# STM32F103.net
KiCad netlist of a schematic drawn in Altium Designer
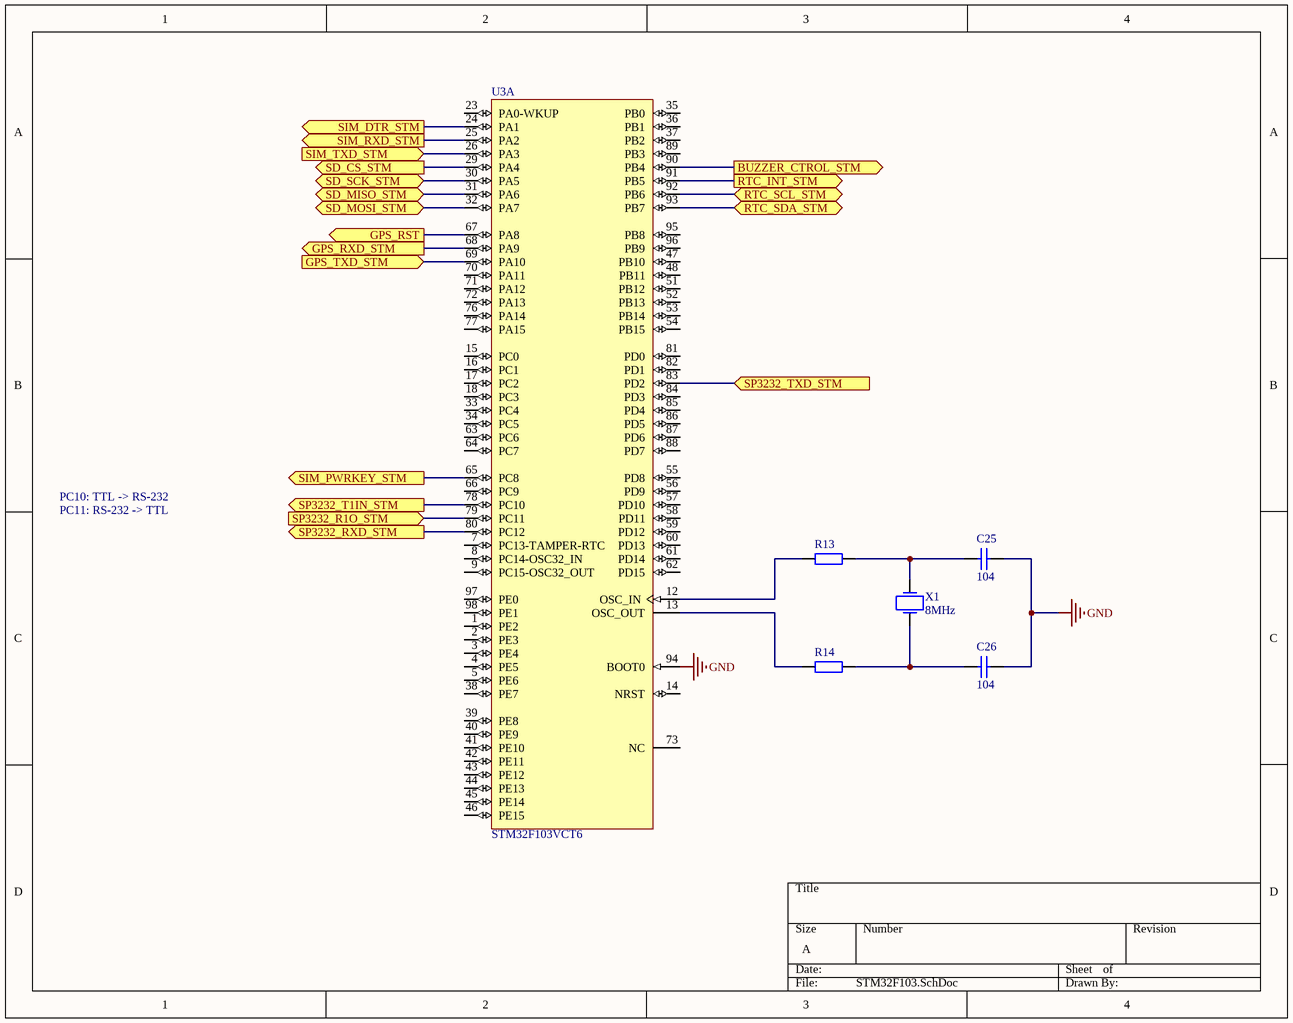
[diagram p0: STM32F103.SchDoc]

(export (version "E")
  (design (tool "Eeschema 10.0.6"))
  (components
    (comp (ref "C25")
      (value "104")
      (footprint "0805")
      (description "Capacitor (Semiconductor SIM Model)")
      (fields (field (name "PUBLISHER") "Altium Limited"))
      (libsource (lib "Devzone_SCHLib") (part "Cap 104_SMD"))
    )
    (comp (ref "C26")
      (value "104")
      (footprint "0805")
      (description "Capacitor (Semiconductor SIM Model)")
      (fields (field (name "PUBLISHER") "Altium Limited"))
      (libsource (lib "Devzone_SCHLib") (part "Cap 104_SMD"))
    )
    (comp (ref "R13")
      (value "~")
      (footprint "RES-1/4W")
      (description "Resistor R1/4W")
      (libsource (lib "KhanhBK_Library_4") (part "R"))
    )
    (comp (ref "R14")
      (value "~")
      (footprint "RES-1/4W")
      (description "Resistor R1/4W")
      (libsource (lib "KhanhBK_Library_4") (part "R"))
    )
    (comp (ref "U3")
      (value "STM32F103VCT6")
      (footprint "STM-LQFP100_M")
      (libsource (lib "KhanhBK_Library_4") (part "STM32F103VCT6"))
    )
    (comp (ref "X1")
      (value "8MHz")
      (footprint "XTAL_THG_HC49/US")
      (description "CRYSTAL 8.0000MHZ 12PF T/H")
      (fields
        (field (name "MANUFACTURER") "TXC CORPORATION")
        (field (name "MANUFACTURER PART NUMBER") "9B-8.000MAAE-B")
      )
      (libsource (lib "KhanhBK_SCH_Lib_6") (part "XTAL_9B-8.000MAAE-B"))
    )
  )
  (nets
    (net (code "1") (name "/BUZZER_CTROL_STM") (class "Default")
      (node (ref "U3") (pin "90") (pinfunction "PB4_90") (pintype "bidirectional"))
    )
    (net (code "2") (name "/GPS_RST") (class "Default")
      (node (ref "U3") (pin "67") (pinfunction "PA8_67") (pintype "bidirectional"))
    )
    (net (code "3") (name "/GPS_RXD_STM") (class "Default")
      (node (ref "U3") (pin "68") (pinfunction "PA9_68") (pintype "bidirectional"))
    )
    (net (code "4") (name "/GPS_TXD_STM") (class "Default")
      (node (ref "U3") (pin "69") (pinfunction "PA10_69") (pintype "bidirectional"))
    )
    (net (code "5") (name "/RTC_INT_STM") (class "Default")
      (node (ref "U3") (pin "91") (pinfunction "PB5_91") (pintype "bidirectional"))
    )
    (net (code "6") (name "/RTC_SCL_STM") (class "Default")
      (node (ref "U3") (pin "92") (pinfunction "PB6_92") (pintype "bidirectional"))
    )
    (net (code "7") (name "/RTC_SDA_STM") (class "Default")
      (node (ref "U3") (pin "93") (pinfunction "PB7_93") (pintype "bidirectional"))
    )
    (net (code "8") (name "/SD_CS_STM") (class "Default")
      (node (ref "U3") (pin "29") (pinfunction "PA4_29") (pintype "bidirectional"))
    )
    (net (code "9") (name "/SD_MISO_STM") (class "Default")
      (node (ref "U3") (pin "31") (pinfunction "PA6_31") (pintype "bidirectional"))
    )
    (net (code "10") (name "/SD_MOSI_STM") (class "Default")
      (node (ref "U3") (pin "32") (pinfunction "PA7_32") (pintype "bidirectional"))
    )
    (net (code "11") (name "/SD_SCK_STM") (class "Default")
      (node (ref "U3") (pin "30") (pinfunction "PA5_30") (pintype "bidirectional"))
    )
    (net (code "12") (name "/SIM_DTR_STM") (class "Default")
      (node (ref "U3") (pin "24") (pinfunction "PA1_24") (pintype "bidirectional"))
    )
    (net (code "13") (name "/SIM_PWRKEY_STM") (class "Default")
      (node (ref "U3") (pin "65") (pinfunction "PC8_65") (pintype "bidirectional"))
    )
    (net (code "14") (name "/SIM_RXD_STM") (class "Default")
      (node (ref "U3") (pin "25") (pinfunction "PA2_25") (pintype "bidirectional"))
    )
    (net (code "15") (name "/SIM_TXD_STM") (class "Default")
      (node (ref "U3") (pin "26") (pinfunction "PA3_26") (pintype "bidirectional"))
    )
    (net (code "16") (name "/SP3232_R1O_STM") (class "Default")
      (node (ref "U3") (pin "79") (pinfunction "PC11_79") (pintype "bidirectional"))
    )
    (net (code "17") (name "/SP3232_RXD_STM") (class "Default")
      (node (ref "U3") (pin "80") (pinfunction "PC12_80") (pintype "bidirectional"))
    )
    (net (code "18") (name "/SP3232_T1IN_STM") (class "Default")
      (node (ref "U3") (pin "78") (pinfunction "PC10_78") (pintype "bidirectional"))
    )
    (net (code "19") (name "/SP3232_TXD_STM") (class "Default")
      (node (ref "U3") (pin "83") (pinfunction "PD2_83") (pintype "bidirectional"))
    )
    (net (code "20") (name "GND") (class "Default")
      (node (ref "C25") (pin "2") (pintype "passive"))
      (node (ref "C26") (pin "2") (pintype "passive"))
      (node (ref "U3") (pin "94") (pinfunction "BOOT0_94") (pintype "input"))
    )
    (net (code "21") (name "Net-(U3A-OSC_IN)") (class "Default")
      (node (ref "R13") (pin "2") (pinfunction "2_2") (pintype "passive"))
      (node (ref "U3") (pin "12") (pinfunction "OSC_IN_12") (pintype "input"))
    )
    (net (code "22") (name "Net-(U3A-OSC_OUT)") (class "Default")
      (node (ref "R14") (pin "2") (pinfunction "2_2") (pintype "passive"))
      (node (ref "U3") (pin "13") (pinfunction "OSC_OUT_13") (pintype "passive"))
    )
    (net (code "23") (name "Net-(X1-OSC1)") (class "Default")
      (node (ref "C26") (pin "1") (pintype "passive"))
      (node (ref "R14") (pin "1") (pinfunction "1_1") (pintype "passive"))
      (node (ref "X1") (pin "1") (pinfunction "OSC1_1") (pintype "passive"))
    )
    (net (code "24") (name "Net-(X1-OSC2)") (class "Default")
      (node (ref "C25") (pin "1") (pintype "passive"))
      (node (ref "R13") (pin "1") (pinfunction "1_1") (pintype "passive"))
      (node (ref "X1") (pin "2") (pinfunction "OSC2_2") (pintype "passive"))
    )
    (net (code "25") (name "unconnected-(U3A-NC-Pad73)") (class "Default")
      (node (ref "U3") (pin "73") (pinfunction "NC_73") (pintype "passive"))
    )
    (net (code "26") (name "unconnected-(U3A-NRST-Pad14)") (class "Default")
      (node (ref "U3") (pin "14") (pinfunction "NRST_14") (pintype "bidirectional"))
    )
    (net (code "27") (name "unconnected-(U3A-PA0-WKUP-Pad23)") (class "Default")
      (node (ref "U3") (pin "23") (pinfunction "PA0-WKUP_23") (pintype "bidirectional"))
    )
    (net (code "28") (name "unconnected-(U3A-PA11-Pad70)") (class "Default")
      (node (ref "U3") (pin "70") (pinfunction "PA11_70") (pintype "bidirectional"))
    )
    (net (code "29") (name "unconnected-(U3A-PA12-Pad71)") (class "Default")
      (node (ref "U3") (pin "71") (pinfunction "PA12_71") (pintype "bidirectional"))
    )
    (net (code "30") (name "unconnected-(U3A-PA13-Pad72)") (class "Default")
      (node (ref "U3") (pin "72") (pinfunction "PA13_72") (pintype "bidirectional"))
    )
    (net (code "31") (name "unconnected-(U3A-PA14-Pad76)") (class "Default")
      (node (ref "U3") (pin "76") (pinfunction "PA14_76") (pintype "bidirectional"))
    )
    (net (code "32") (name "unconnected-(U3A-PA15-Pad77)") (class "Default")
      (node (ref "U3") (pin "77") (pinfunction "PA15_77") (pintype "bidirectional"))
    )
    (net (code "33") (name "unconnected-(U3A-PB0-Pad35)") (class "Default")
      (node (ref "U3") (pin "35") (pinfunction "PB0_35") (pintype "bidirectional"))
    )
    (net (code "34") (name "unconnected-(U3A-PB1-Pad36)") (class "Default")
      (node (ref "U3") (pin "36") (pinfunction "PB1_36") (pintype "bidirectional"))
    )
    (net (code "35") (name "unconnected-(U3A-PB2-Pad37)") (class "Default")
      (node (ref "U3") (pin "37") (pinfunction "PB2_37") (pintype "bidirectional"))
    )
    (net (code "36") (name "unconnected-(U3A-PB3-Pad89)") (class "Default")
      (node (ref "U3") (pin "89") (pinfunction "PB3_89") (pintype "bidirectional"))
    )
    (net (code "37") (name "unconnected-(U3A-PB8-Pad95)") (class "Default")
      (node (ref "U3") (pin "95") (pinfunction "PB8_95") (pintype "bidirectional"))
    )
    (net (code "38") (name "unconnected-(U3A-PB9-Pad96)") (class "Default")
      (node (ref "U3") (pin "96") (pinfunction "PB9_96") (pintype "bidirectional"))
    )
    (net (code "39") (name "unconnected-(U3A-PB10-Pad47)") (class "Default")
      (node (ref "U3") (pin "47") (pinfunction "PB10_47") (pintype "bidirectional"))
    )
    (net (code "40") (name "unconnected-(U3A-PB11-Pad48)") (class "Default")
      (node (ref "U3") (pin "48") (pinfunction "PB11_48") (pintype "bidirectional"))
    )
    (net (code "41") (name "unconnected-(U3A-PB12-Pad51)") (class "Default")
      (node (ref "U3") (pin "51") (pinfunction "PB12_51") (pintype "bidirectional"))
    )
    (net (code "42") (name "unconnected-(U3A-PB13-Pad52)") (class "Default")
      (node (ref "U3") (pin "52") (pinfunction "PB13_52") (pintype "bidirectional"))
    )
    (net (code "43") (name "unconnected-(U3A-PB14-Pad53)") (class "Default")
      (node (ref "U3") (pin "53") (pinfunction "PB14_53") (pintype "bidirectional"))
    )
    (net (code "44") (name "unconnected-(U3A-PB15-Pad54)") (class "Default")
      (node (ref "U3") (pin "54") (pinfunction "PB15_54") (pintype "bidirectional"))
    )
    (net (code "45") (name "unconnected-(U3A-PC0-Pad15)") (class "Default")
      (node (ref "U3") (pin "15") (pinfunction "PC0_15") (pintype "bidirectional"))
    )
    (net (code "46") (name "unconnected-(U3A-PC1-Pad16)") (class "Default")
      (node (ref "U3") (pin "16") (pinfunction "PC1_16") (pintype "bidirectional"))
    )
    (net (code "47") (name "unconnected-(U3A-PC2-Pad17)") (class "Default")
      (node (ref "U3") (pin "17") (pinfunction "PC2_17") (pintype "bidirectional"))
    )
    (net (code "48") (name "unconnected-(U3A-PC3-Pad18)") (class "Default")
      (node (ref "U3") (pin "18") (pinfunction "PC3_18") (pintype "bidirectional"))
    )
    (net (code "49") (name "unconnected-(U3A-PC4-Pad33)") (class "Default")
      (node (ref "U3") (pin "33") (pinfunction "PC4_33") (pintype "bidirectional"))
    )
    (net (code "50") (name "unconnected-(U3A-PC5-Pad34)") (class "Default")
      (node (ref "U3") (pin "34") (pinfunction "PC5_34") (pintype "bidirectional"))
    )
    (net (code "51") (name "unconnected-(U3A-PC6-Pad63)") (class "Default")
      (node (ref "U3") (pin "63") (pinfunction "PC6_63") (pintype "bidirectional"))
    )
    (net (code "52") (name "unconnected-(U3A-PC7-Pad64)") (class "Default")
      (node (ref "U3") (pin "64") (pinfunction "PC7_64") (pintype "bidirectional"))
    )
    (net (code "53") (name "unconnected-(U3A-PC9-Pad66)") (class "Default")
      (node (ref "U3") (pin "66") (pinfunction "PC9_66") (pintype "bidirectional"))
    )
    (net (code "54") (name "unconnected-(U3A-PC13-TAMPER-RTC-Pad7)") (class "Default")
      (node (ref "U3") (pin "7") (pinfunction "PC13-TAMPER-RTC_7") (pintype "bidirectional"))
    )
    (net (code "55") (name "unconnected-(U3A-PC14-OSC32_IN-Pad8)") (class "Default")
      (node (ref "U3") (pin "8") (pinfunction "PC14-OSC32_IN_8") (pintype "bidirectional"))
    )
    (net (code "56") (name "unconnected-(U3A-PC15-OSC32_OUT-Pad9)") (class "Default")
      (node (ref "U3") (pin "9") (pinfunction "PC15-OSC32_OUT_9") (pintype "bidirectional"))
    )
    (net (code "57") (name "unconnected-(U3A-PD0-Pad81)") (class "Default")
      (node (ref "U3") (pin "81") (pinfunction "PD0_81") (pintype "bidirectional"))
    )
    (net (code "58") (name "unconnected-(U3A-PD1-Pad82)") (class "Default")
      (node (ref "U3") (pin "82") (pinfunction "PD1_82") (pintype "bidirectional"))
    )
    (net (code "59") (name "unconnected-(U3A-PD3-Pad84)") (class "Default")
      (node (ref "U3") (pin "84") (pinfunction "PD3_84") (pintype "bidirectional"))
    )
    (net (code "60") (name "unconnected-(U3A-PD4-Pad85)") (class "Default")
      (node (ref "U3") (pin "85") (pinfunction "PD4_85") (pintype "bidirectional"))
    )
    (net (code "61") (name "unconnected-(U3A-PD5-Pad86)") (class "Default")
      (node (ref "U3") (pin "86") (pinfunction "PD5_86") (pintype "bidirectional"))
    )
    (net (code "62") (name "unconnected-(U3A-PD6-Pad87)") (class "Default")
      (node (ref "U3") (pin "87") (pinfunction "PD6_87") (pintype "bidirectional"))
    )
    (net (code "63") (name "unconnected-(U3A-PD7-Pad88)") (class "Default")
      (node (ref "U3") (pin "88") (pinfunction "PD7_88") (pintype "bidirectional"))
    )
    (net (code "64") (name "unconnected-(U3A-PD8-Pad55)") (class "Default")
      (node (ref "U3") (pin "55") (pinfunction "PD8_55") (pintype "bidirectional"))
    )
    (net (code "65") (name "unconnected-(U3A-PD9-Pad56)") (class "Default")
      (node (ref "U3") (pin "56") (pinfunction "PD9_56") (pintype "bidirectional"))
    )
    (net (code "66") (name "unconnected-(U3A-PD10-Pad57)") (class "Default")
      (node (ref "U3") (pin "57") (pinfunction "PD10_57") (pintype "bidirectional"))
    )
    (net (code "67") (name "unconnected-(U3A-PD11-Pad58)") (class "Default")
      (node (ref "U3") (pin "58") (pinfunction "PD11_58") (pintype "bidirectional"))
    )
    (net (code "68") (name "unconnected-(U3A-PD12-Pad59)") (class "Default")
      (node (ref "U3") (pin "59") (pinfunction "PD12_59") (pintype "bidirectional"))
    )
    (net (code "69") (name "unconnected-(U3A-PD13-Pad60)") (class "Default")
      (node (ref "U3") (pin "60") (pinfunction "PD13_60") (pintype "bidirectional"))
    )
    (net (code "70") (name "unconnected-(U3A-PD14-Pad61)") (class "Default")
      (node (ref "U3") (pin "61") (pinfunction "PD14_61") (pintype "bidirectional"))
    )
    (net (code "71") (name "unconnected-(U3A-PD15-Pad62)") (class "Default")
      (node (ref "U3") (pin "62") (pinfunction "PD15_62") (pintype "bidirectional"))
    )
    (net (code "72") (name "unconnected-(U3A-PE0-Pad97)") (class "Default")
      (node (ref "U3") (pin "97") (pinfunction "PE0_97") (pintype "bidirectional"))
    )
    (net (code "73") (name "unconnected-(U3A-PE1-Pad98)") (class "Default")
      (node (ref "U3") (pin "98") (pinfunction "PE1_98") (pintype "bidirectional"))
    )
    (net (code "74") (name "unconnected-(U3A-PE2-Pad1)") (class "Default")
      (node (ref "U3") (pin "1") (pinfunction "PE2_1") (pintype "bidirectional"))
    )
    (net (code "75") (name "unconnected-(U3A-PE3-Pad2)") (class "Default")
      (node (ref "U3") (pin "2") (pinfunction "PE3_2") (pintype "bidirectional"))
    )
    (net (code "76") (name "unconnected-(U3A-PE4-Pad3)") (class "Default")
      (node (ref "U3") (pin "3") (pinfunction "PE4_3") (pintype "bidirectional"))
    )
    (net (code "77") (name "unconnected-(U3A-PE5-Pad4)") (class "Default")
      (node (ref "U3") (pin "4") (pinfunction "PE5_4") (pintype "bidirectional"))
    )
    (net (code "78") (name "unconnected-(U3A-PE6-Pad5)") (class "Default")
      (node (ref "U3") (pin "5") (pinfunction "PE6_5") (pintype "bidirectional"))
    )
    (net (code "79") (name "unconnected-(U3A-PE7-Pad38)") (class "Default")
      (node (ref "U3") (pin "38") (pinfunction "PE7_38") (pintype "bidirectional"))
    )
    (net (code "80") (name "unconnected-(U3A-PE8-Pad39)") (class "Default")
      (node (ref "U3") (pin "39") (pinfunction "PE8_39") (pintype "bidirectional"))
    )
    (net (code "81") (name "unconnected-(U3A-PE9-Pad40)") (class "Default")
      (node (ref "U3") (pin "40") (pinfunction "PE9_40") (pintype "bidirectional"))
    )
    (net (code "82") (name "unconnected-(U3A-PE10-Pad41)") (class "Default")
      (node (ref "U3") (pin "41") (pinfunction "PE10_41") (pintype "bidirectional"))
    )
    (net (code "83") (name "unconnected-(U3A-PE11-Pad42)") (class "Default")
      (node (ref "U3") (pin "42") (pinfunction "PE11_42") (pintype "bidirectional"))
    )
    (net (code "84") (name "unconnected-(U3A-PE12-Pad43)") (class "Default")
      (node (ref "U3") (pin "43") (pinfunction "PE12_43") (pintype "bidirectional"))
    )
    (net (code "85") (name "unconnected-(U3A-PE13-Pad44)") (class "Default")
      (node (ref "U3") (pin "44") (pinfunction "PE13_44") (pintype "bidirectional"))
    )
    (net (code "86") (name "unconnected-(U3A-PE14-Pad45)") (class "Default")
      (node (ref "U3") (pin "45") (pinfunction "PE14_45") (pintype "bidirectional"))
    )
    (net (code "87") (name "unconnected-(U3A-PE15-Pad46)") (class "Default")
      (node (ref "U3") (pin "46") (pinfunction "PE15_46") (pintype "bidirectional"))
    )
  )
)
